# simblee_gate.net
KiCad netlist of a schematic drawn in EAGLE
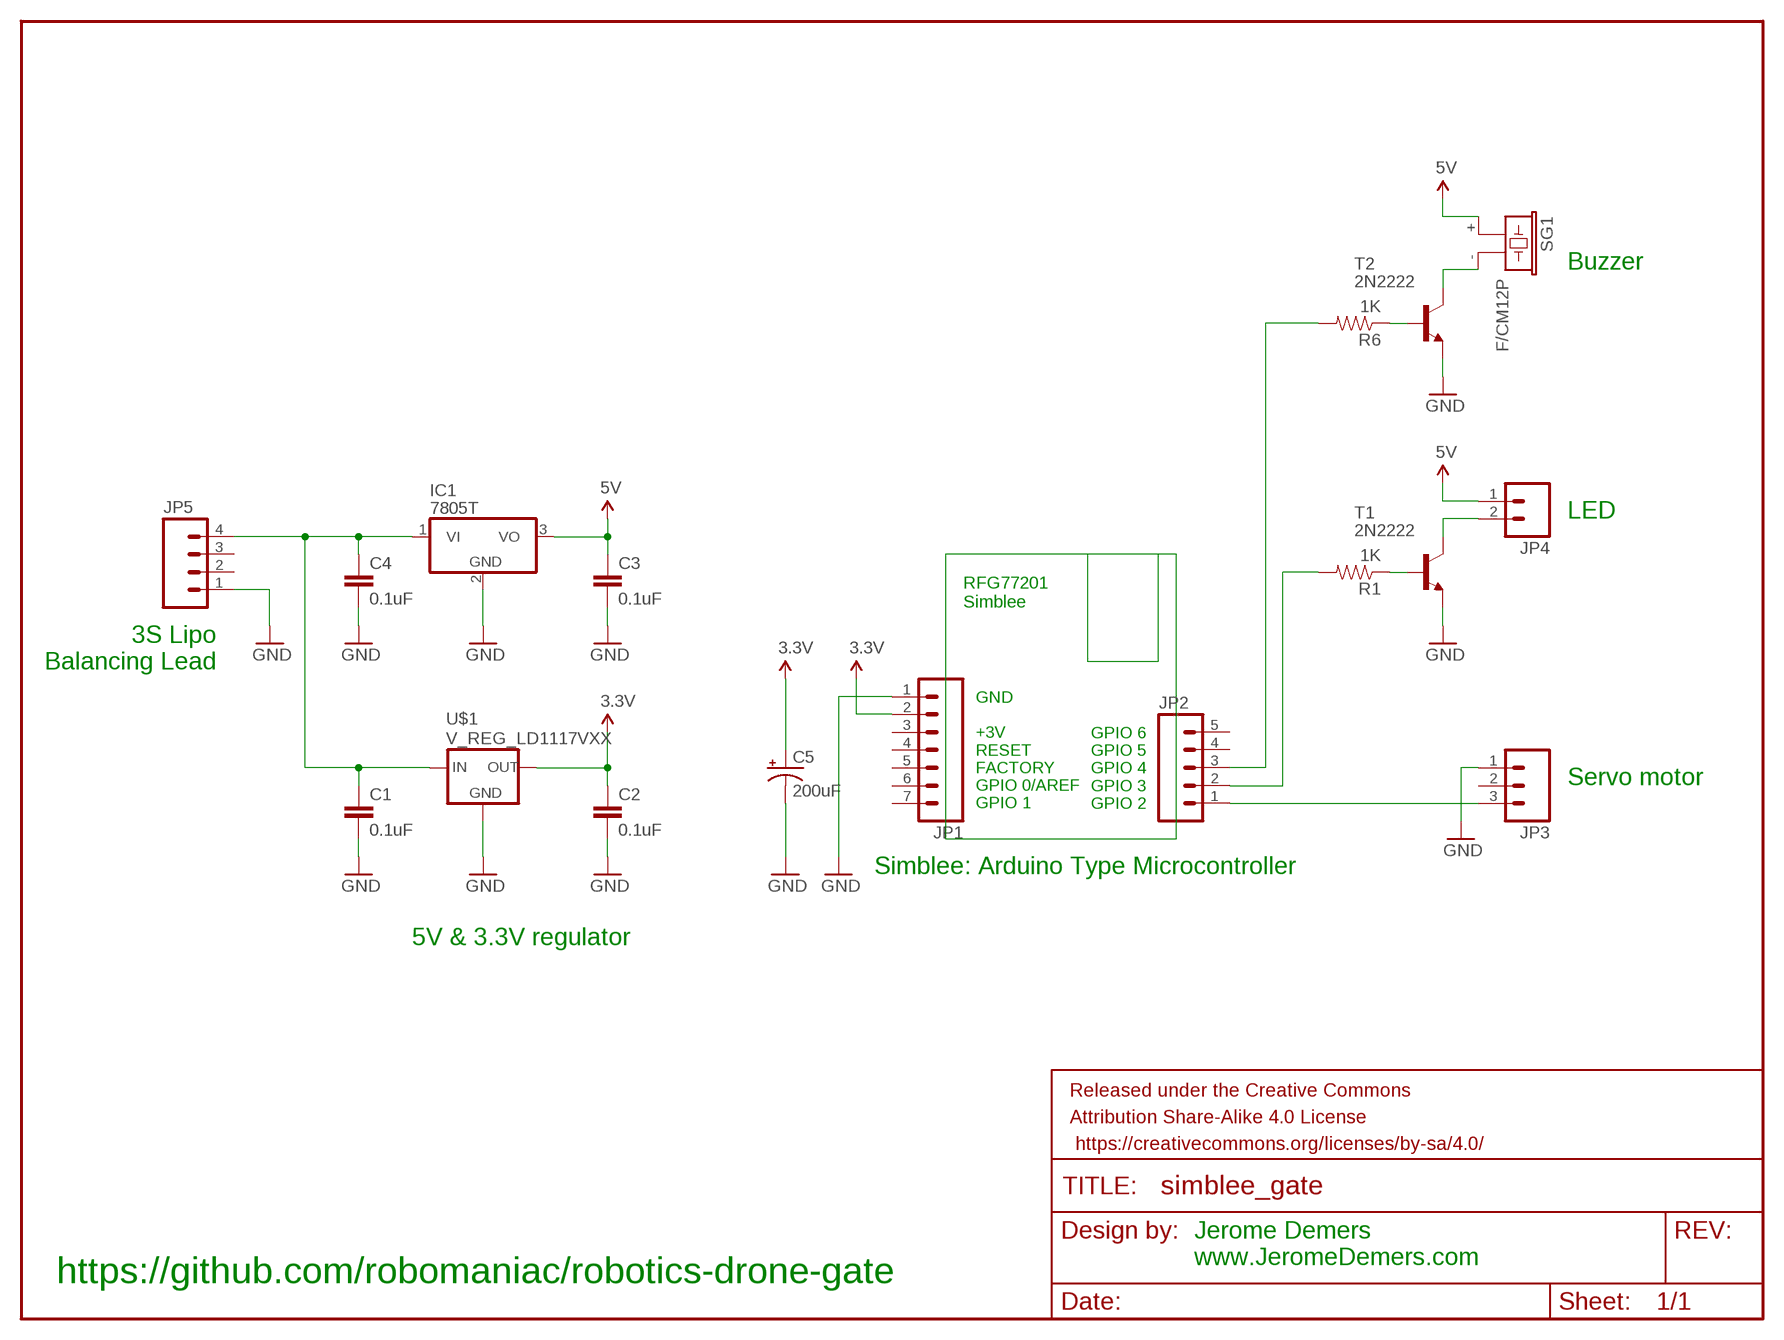
[diagram p0: schematic, sheet 1]

(export (version "E")
  (design (tool "Eeschema 10.0.6"))
  (components
    (comp (ref "C1")
      (value "0.1uF")
      (footprint "eagle-import:0603-CAP")
      (libsource (lib "eagle-import") (part "0.1UF-25V(+80/-20%)(0603)"))
    )
    (comp (ref "C2")
      (value "0.1uF")
      (footprint "eagle-import:0603-CAP")
      (libsource (lib "eagle-import") (part "0.1UF-25V(+80/-20%)(0603)"))
    )
    (comp (ref "C3")
      (value "0.1uF")
      (footprint "eagle-import:0603-CAP")
      (libsource (lib "eagle-import") (part "0.1UF-25V(+80/-20%)(0603)"))
    )
    (comp (ref "C4")
      (value "0.1uF")
      (footprint "eagle-import:0603-CAP")
      (libsource (lib "eagle-import") (part "0.1UF-25V(+80/-20%)(0603)"))
    )
    (comp (ref "C5")
      (value "200uF")
      (footprint "eagle-import:CPOL-RADIAL-100UF-25V")
      (libsource (lib "eagle-import") (part "100UF-25V-20%(PTH)"))
    )
    (comp (ref "FRAME1")
      (value "FRAME-LETTER")
      (footprint "eagle-import:CREATIVE_COMMONS")
      (libsource (lib "eagle-import") (part "FRAME-LETTER"))
    )
    (comp (ref "IC1")
      (value "7805T")
      (footprint "eagle-import:TO220H")
      (libsource (lib "eagle-import") (part "78T05"))
    )
    (comp (ref "JP1")
      (value "M07")
      (footprint "eagle-import:1X07")
      (libsource (lib "eagle-import") (part "M07"))
    )
    (comp (ref "JP2")
      (value "M05PTH")
      (footprint "eagle-import:1X05")
      (libsource (lib "eagle-import") (part "M05PTH"))
    )
    (comp (ref "JP3")
      (value "M03PTH")
      (footprint "eagle-import:1X03")
      (libsource (lib "eagle-import") (part "M03PTH"))
    )
    (comp (ref "JP4")
      (value "M02JST-PTH-VERT")
      (footprint "eagle-import:JST-2-PTH-VERT")
      (libsource (lib "eagle-import") (part "M02JST-PTH-VERT"))
    )
    (comp (ref "JP5")
      (value "M04POLAR")
      (footprint "eagle-import:MOLEX-1X4")
      (libsource (lib "eagle-import") (part "M04POLAR"))
    )
    (comp (ref "R1")
      (value "1K")
      (footprint "eagle-import:0805")
      (libsource (lib "eagle-import") (part "RESISTOR0805-RES"))
    )
    (comp (ref "R6")
      (value "1K")
      (footprint "eagle-import:0805")
      (libsource (lib "eagle-import") (part "RESISTOR0805-RES"))
    )
    (comp (ref "SG1")
      (value "F/CM12P")
      (footprint "eagle-import:F_CM12P")
      (libsource (lib "eagle-import") (part "F/CM12P"))
    )
    (comp (ref "T1")
      (value "2N2222")
      (footprint "eagle-import:TO92-EBC-OVAL")
      (libsource (lib "eagle-import") (part "2N2222"))
    )
    (comp (ref "T2")
      (value "2N2222")
      (footprint "eagle-import:TO92-EBC-OVAL")
      (libsource (lib "eagle-import") (part "2N2222"))
    )
    (comp (ref "U$1")
      (value "V_REG_LD1117VXX")
      (footprint "eagle-import:78XXL")
      (libsource (lib "eagle-import") (part "V_REG_LD1117VXX"))
    )
  )
  (nets
    (net (code "1") (name "3.3V") (class "Default")
      (node (ref "C2") (pin "1") (pinfunction "1_1") (pintype "passive"))
      (node (ref "C5") (pin "1") (pinfunction "+_1") (pintype "passive"))
      (node (ref "JP1") (pin "2") (pinfunction "2_2") (pintype "passive"))
      (node (ref "U$1") (pin "GND") (pinfunction "OUT_GND") (pintype "passive"))
    )
    (net (code "2") (name "5V") (class "Default")
      (node (ref "C3") (pin "1") (pinfunction "1_1") (pintype "passive"))
      (node (ref "IC1") (pin "3") (pinfunction "VO_3") (pintype "passive"))
      (node (ref "JP4") (pin "1") (pinfunction "1_1") (pintype "passive"))
      (node (ref "SG1") (pin "+") (pinfunction "1_+") (pintype "passive"))
    )
    (net (code "3") (name "GND") (class "Default")
      (node (ref "C1") (pin "2") (pinfunction "2_2") (pintype "passive"))
      (node (ref "C2") (pin "2") (pinfunction "2_2") (pintype "passive"))
      (node (ref "C3") (pin "2") (pinfunction "2_2") (pintype "passive"))
      (node (ref "C4") (pin "2") (pinfunction "2_2") (pintype "passive"))
      (node (ref "C5") (pin "2") (pinfunction "-_2") (pintype "passive"))
      (node (ref "IC1") (pin "2") (pinfunction "GND_2") (pintype "passive"))
      (node (ref "JP1") (pin "1") (pinfunction "1_1") (pintype "passive"))
      (node (ref "JP3") (pin "1") (pinfunction "1_1") (pintype "passive"))
      (node (ref "JP5") (pin "1") (pinfunction "1_1") (pintype "passive"))
      (node (ref "T1") (pin "E") (pinfunction "E_E") (pintype "passive"))
      (node (ref "T2") (pin "E") (pinfunction "E_E") (pintype "passive"))
      (node (ref "U$1") (pin "IN") (pinfunction "GND_IN") (pintype "input"))
    )
    (net (code "4") (name "Net-(IC1-VI)") (class "Default")
      (node (ref "C1") (pin "1") (pinfunction "1_1") (pintype "passive"))
      (node (ref "C4") (pin "1") (pinfunction "1_1") (pintype "passive"))
      (node (ref "IC1") (pin "1") (pinfunction "VI_1") (pintype "input"))
      (node (ref "JP5") (pin "4") (pinfunction "4_4") (pintype "passive"))
      (node (ref "U$1") (pin "OUT") (pinfunction "IN_OUT") (pintype "input"))
    )
    (net (code "5") (name "Net-(JP2-Pad1)") (class "Default")
      (node (ref "JP2") (pin "1") (pinfunction "1_1") (pintype "passive"))
      (node (ref "JP3") (pin "3") (pinfunction "3_3") (pintype "passive"))
    )
    (net (code "6") (name "Net-(JP2-Pad2)") (class "Default")
      (node (ref "JP2") (pin "2") (pinfunction "2_2") (pintype "passive"))
      (node (ref "R1") (pin "2") (pinfunction "2_2") (pintype "passive"))
    )
    (net (code "7") (name "Net-(JP2-Pad3)") (class "Default")
      (node (ref "JP2") (pin "3") (pinfunction "3_3") (pintype "passive"))
      (node (ref "R6") (pin "2") (pinfunction "2_2") (pintype "passive"))
    )
    (net (code "8") (name "Net-(JP4-Pad2)") (class "Default")
      (node (ref "JP4") (pin "2") (pinfunction "2_2") (pintype "passive"))
      (node (ref "T1") (pin "C") (pinfunction "C_C") (pintype "passive"))
    )
    (net (code "9") (name "Net-(R1-Pad1)") (class "Default")
      (node (ref "R1") (pin "1") (pinfunction "1_1") (pintype "passive"))
      (node (ref "T1") (pin "B") (pinfunction "B_B") (pintype "passive"))
    )
    (net (code "10") (name "Net-(R6-Pad1)") (class "Default")
      (node (ref "R6") (pin "1") (pinfunction "1_1") (pintype "passive"))
      (node (ref "T2") (pin "B") (pinfunction "B_B") (pintype "passive"))
    )
    (net (code "11") (name "Net-(SG1-2)") (class "Default")
      (node (ref "SG1") (pin "-") (pinfunction "2_-") (pintype "passive"))
      (node (ref "T2") (pin "C") (pinfunction "C_C") (pintype "passive"))
    )
    (net (code "12") (name "unconnected-(JP1-Pad3)") (class "Default")
      (node (ref "JP1") (pin "3") (pinfunction "3_3") (pintype "passive"))
    )
    (net (code "13") (name "unconnected-(JP1-Pad4)") (class "Default")
      (node (ref "JP1") (pin "4") (pinfunction "4_4") (pintype "passive"))
    )
    (net (code "14") (name "unconnected-(JP1-Pad5)") (class "Default")
      (node (ref "JP1") (pin "5") (pinfunction "5_5") (pintype "passive"))
    )
    (net (code "15") (name "unconnected-(JP1-Pad6)") (class "Default")
      (node (ref "JP1") (pin "6") (pinfunction "6_6") (pintype "passive"))
    )
    (net (code "16") (name "unconnected-(JP1-Pad7)") (class "Default")
      (node (ref "JP1") (pin "7") (pinfunction "7_7") (pintype "passive"))
    )
    (net (code "17") (name "unconnected-(JP2-Pad4)") (class "Default")
      (node (ref "JP2") (pin "4") (pinfunction "4_4") (pintype "passive"))
    )
    (net (code "18") (name "unconnected-(JP2-Pad5)") (class "Default")
      (node (ref "JP2") (pin "5") (pinfunction "5_5") (pintype "passive"))
    )
    (net (code "19") (name "unconnected-(JP3-Pad2)") (class "Default")
      (node (ref "JP3") (pin "2") (pinfunction "2_2") (pintype "passive"))
    )
    (net (code "20") (name "unconnected-(JP5-Pad2)") (class "Default")
      (node (ref "JP5") (pin "2") (pinfunction "2_2") (pintype "passive"))
    )
    (net (code "21") (name "unconnected-(JP5-Pad3)") (class "Default")
      (node (ref "JP5") (pin "3") (pinfunction "3_3") (pintype "passive"))
    )
  )
)
